# 6_half_bridge.net
KiCad netlist of a schematic drawn in Altium Designer
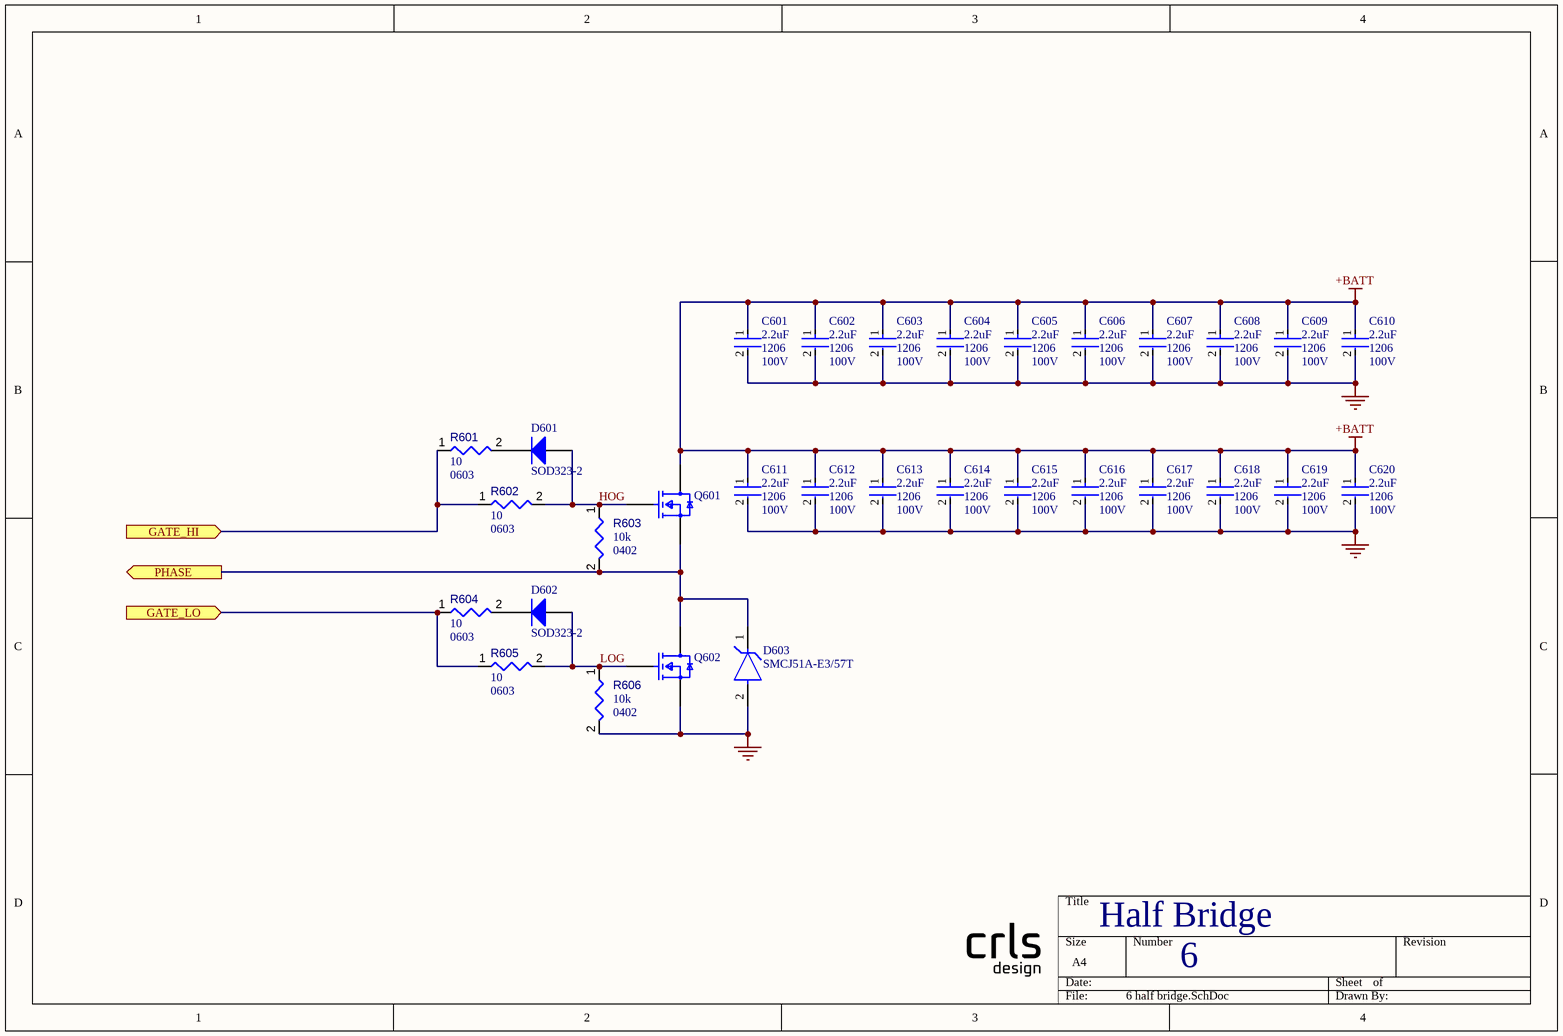
[diagram p0: 6 half bridge.SchDoc]

(export (version "E")
  (design (tool "Eeschema 10.0.6"))
  (components
    (comp (ref "C601")
      (value "CC1206KKX7R0BB225")
      (footprint "FP-CC1206-0_3-1_9-MFG")
      (description "CAP CER 2.2UF 100V X7R 1206")
      (fields
        (field (name "VOLTAGE RATING") "100V")
        (field (name "CASE/PACKAGE") "1206")
        (field (name "CAPACITANCE") "2.2uF")
        (field (name "TOLERANCE") "10%")
      )
      (libsource (lib "Altium Content Vault") (part "b4654b650e69147ec39a6b967a45e02"))
    )
    (comp (ref "C602")
      (value "CC1206KKX7R0BB225")
      (footprint "FP-CC1206-0_3-1_9-MFG")
      (description "CAP CER 2.2UF 100V X7R 1206")
      (fields
        (field (name "VOLTAGE RATING") "100V")
        (field (name "CASE/PACKAGE") "1206")
        (field (name "CAPACITANCE") "2.2uF")
        (field (name "TOLERANCE") "10%")
      )
      (libsource (lib "Altium Content Vault") (part "b4654b650e69147ec39a6b967a45e02"))
    )
    (comp (ref "C603")
      (value "CC1206KKX7R0BB225")
      (footprint "FP-CC1206-0_3-1_9-MFG")
      (description "CAP CER 2.2UF 100V X7R 1206")
      (fields
        (field (name "VOLTAGE RATING") "100V")
        (field (name "CASE/PACKAGE") "1206")
        (field (name "CAPACITANCE") "2.2uF")
        (field (name "TOLERANCE") "10%")
      )
      (libsource (lib "Altium Content Vault") (part "b4654b650e69147ec39a6b967a45e02"))
    )
    (comp (ref "C604")
      (value "CC1206KKX7R0BB225")
      (footprint "FP-CC1206-0_3-1_9-MFG")
      (description "CAP CER 2.2UF 100V X7R 1206")
      (fields
        (field (name "VOLTAGE RATING") "100V")
        (field (name "CASE/PACKAGE") "1206")
        (field (name "CAPACITANCE") "2.2uF")
        (field (name "TOLERANCE") "10%")
      )
      (libsource (lib "Altium Content Vault") (part "b4654b650e69147ec39a6b967a45e02"))
    )
    (comp (ref "C605")
      (value "CC1206KKX7R0BB225")
      (footprint "FP-CC1206-0_3-1_9-MFG")
      (description "CAP CER 2.2UF 100V X7R 1206")
      (fields
        (field (name "VOLTAGE RATING") "100V")
        (field (name "CASE/PACKAGE") "1206")
        (field (name "CAPACITANCE") "2.2uF")
        (field (name "TOLERANCE") "10%")
      )
      (libsource (lib "Altium Content Vault") (part "b4654b650e69147ec39a6b967a45e02"))
    )
    (comp (ref "C606")
      (value "CC1206KKX7R0BB225")
      (footprint "FP-CC1206-0_3-1_9-MFG")
      (description "CAP CER 2.2UF 100V X7R 1206")
      (fields
        (field (name "VOLTAGE RATING") "100V")
        (field (name "CASE/PACKAGE") "1206")
        (field (name "CAPACITANCE") "2.2uF")
        (field (name "TOLERANCE") "10%")
      )
      (libsource (lib "Altium Content Vault") (part "b4654b650e69147ec39a6b967a45e02"))
    )
    (comp (ref "C607")
      (value "CC1206KKX7R0BB225")
      (footprint "FP-CC1206-0_3-1_9-MFG")
      (description "CAP CER 2.2UF 100V X7R 1206")
      (fields
        (field (name "VOLTAGE RATING") "100V")
        (field (name "CASE/PACKAGE") "1206")
        (field (name "CAPACITANCE") "2.2uF")
        (field (name "TOLERANCE") "10%")
      )
      (libsource (lib "Altium Content Vault") (part "b4654b650e69147ec39a6b967a45e02"))
    )
    (comp (ref "C608")
      (value "CC1206KKX7R0BB225")
      (footprint "FP-CC1206-0_3-1_9-MFG")
      (description "CAP CER 2.2UF 100V X7R 1206")
      (fields
        (field (name "VOLTAGE RATING") "100V")
        (field (name "CASE/PACKAGE") "1206")
        (field (name "CAPACITANCE") "2.2uF")
        (field (name "TOLERANCE") "10%")
      )
      (libsource (lib "Altium Content Vault") (part "b4654b650e69147ec39a6b967a45e02"))
    )
    (comp (ref "C609")
      (value "CC1206KKX7R0BB225")
      (footprint "FP-CC1206-0_3-1_9-MFG")
      (description "CAP CER 2.2UF 100V X7R 1206")
      (fields
        (field (name "VOLTAGE RATING") "100V")
        (field (name "CASE/PACKAGE") "1206")
        (field (name "CAPACITANCE") "2.2uF")
        (field (name "TOLERANCE") "10%")
      )
      (libsource (lib "Altium Content Vault") (part "b4654b650e69147ec39a6b967a45e02"))
    )
    (comp (ref "C610")
      (value "CC1206KKX7R0BB225")
      (footprint "FP-CC1206-0_3-1_9-MFG")
      (description "CAP CER 2.2UF 100V X7R 1206")
      (fields
        (field (name "VOLTAGE RATING") "100V")
        (field (name "CASE/PACKAGE") "1206")
        (field (name "CAPACITANCE") "2.2uF")
        (field (name "TOLERANCE") "10%")
      )
      (libsource (lib "Altium Content Vault") (part "b4654b650e69147ec39a6b967a45e02"))
    )
    (comp (ref "C611")
      (value "CC1206KKX7R0BB225")
      (footprint "FP-CC1206-0_3-1_9-MFG")
      (description "CAP CER 2.2UF 100V X7R 1206")
      (fields
        (field (name "VOLTAGE RATING") "100V")
        (field (name "CASE/PACKAGE") "1206")
        (field (name "CAPACITANCE") "2.2uF")
        (field (name "TOLERANCE") "10%")
      )
      (libsource (lib "Altium Content Vault") (part "b4654b650e69147ec39a6b967a45e02"))
    )
    (comp (ref "C612")
      (value "CC1206KKX7R0BB225")
      (footprint "FP-CC1206-0_3-1_9-MFG")
      (description "CAP CER 2.2UF 100V X7R 1206")
      (fields
        (field (name "VOLTAGE RATING") "100V")
        (field (name "CASE/PACKAGE") "1206")
        (field (name "CAPACITANCE") "2.2uF")
        (field (name "TOLERANCE") "10%")
      )
      (libsource (lib "Altium Content Vault") (part "b4654b650e69147ec39a6b967a45e02"))
    )
    (comp (ref "C613")
      (value "CC1206KKX7R0BB225")
      (footprint "FP-CC1206-0_3-1_9-MFG")
      (description "CAP CER 2.2UF 100V X7R 1206")
      (fields
        (field (name "VOLTAGE RATING") "100V")
        (field (name "CASE/PACKAGE") "1206")
        (field (name "CAPACITANCE") "2.2uF")
        (field (name "TOLERANCE") "10%")
      )
      (libsource (lib "Altium Content Vault") (part "b4654b650e69147ec39a6b967a45e02"))
    )
    (comp (ref "C614")
      (value "CC1206KKX7R0BB225")
      (footprint "FP-CC1206-0_3-1_9-MFG")
      (description "CAP CER 2.2UF 100V X7R 1206")
      (fields
        (field (name "VOLTAGE RATING") "100V")
        (field (name "CASE/PACKAGE") "1206")
        (field (name "CAPACITANCE") "2.2uF")
        (field (name "TOLERANCE") "10%")
      )
      (libsource (lib "Altium Content Vault") (part "b4654b650e69147ec39a6b967a45e02"))
    )
    (comp (ref "C615")
      (value "CC1206KKX7R0BB225")
      (footprint "FP-CC1206-0_3-1_9-MFG")
      (description "CAP CER 2.2UF 100V X7R 1206")
      (fields
        (field (name "VOLTAGE RATING") "100V")
        (field (name "CASE/PACKAGE") "1206")
        (field (name "CAPACITANCE") "2.2uF")
        (field (name "TOLERANCE") "10%")
      )
      (libsource (lib "Altium Content Vault") (part "b4654b650e69147ec39a6b967a45e02"))
    )
    (comp (ref "C616")
      (value "CC1206KKX7R0BB225")
      (footprint "FP-CC1206-0_3-1_9-MFG")
      (description "CAP CER 2.2UF 100V X7R 1206")
      (fields
        (field (name "VOLTAGE RATING") "100V")
        (field (name "CASE/PACKAGE") "1206")
        (field (name "CAPACITANCE") "2.2uF")
        (field (name "TOLERANCE") "10%")
      )
      (libsource (lib "Altium Content Vault") (part "b4654b650e69147ec39a6b967a45e02"))
    )
    (comp (ref "C617")
      (value "CC1206KKX7R0BB225")
      (footprint "FP-CC1206-0_3-1_9-MFG")
      (description "CAP CER 2.2UF 100V X7R 1206")
      (fields
        (field (name "VOLTAGE RATING") "100V")
        (field (name "CASE/PACKAGE") "1206")
        (field (name "CAPACITANCE") "2.2uF")
        (field (name "TOLERANCE") "10%")
      )
      (libsource (lib "Altium Content Vault") (part "b4654b650e69147ec39a6b967a45e02"))
    )
    (comp (ref "C618")
      (value "CC1206KKX7R0BB225")
      (footprint "FP-CC1206-0_3-1_9-MFG")
      (description "CAP CER 2.2UF 100V X7R 1206")
      (fields
        (field (name "VOLTAGE RATING") "100V")
        (field (name "CASE/PACKAGE") "1206")
        (field (name "CAPACITANCE") "2.2uF")
        (field (name "TOLERANCE") "10%")
      )
      (libsource (lib "Altium Content Vault") (part "b4654b650e69147ec39a6b967a45e02"))
    )
    (comp (ref "C619")
      (value "CC1206KKX7R0BB225")
      (footprint "FP-CC1206-0_3-1_9-MFG")
      (description "CAP CER 2.2UF 100V X7R 1206")
      (fields
        (field (name "VOLTAGE RATING") "100V")
        (field (name "CASE/PACKAGE") "1206")
        (field (name "CAPACITANCE") "2.2uF")
        (field (name "TOLERANCE") "10%")
      )
      (libsource (lib "Altium Content Vault") (part "b4654b650e69147ec39a6b967a45e02"))
    )
    (comp (ref "C620")
      (value "CC1206KKX7R0BB225")
      (footprint "FP-CC1206-0_3-1_9-MFG")
      (description "CAP CER 2.2UF 100V X7R 1206")
      (fields
        (field (name "VOLTAGE RATING") "100V")
        (field (name "CASE/PACKAGE") "1206")
        (field (name "CAPACITANCE") "2.2uF")
        (field (name "TOLERANCE") "10%")
      )
      (libsource (lib "Altium Content Vault") (part "b4654b650e69147ec39a6b967a45e02"))
    )
    (comp (ref "D601")
      (value "1N4148WS-7-F")
      (footprint "DIOD-SOD323-2-A_V")
      (description "Fast Switching Diode, 75 V, 0.3 A, -65 to 150 degC, 2-Pin SOD323, RoHS, Tape and Reel")
      (fields (field (name "PACKAGEREFERENCE") "SOD323-2"))
      (libsource (lib "Altium Content Vault") (part "D-AK-2"))
    )
    (comp (ref "D602")
      (value "1N4148WS-7-F")
      (footprint "DIOD-SOD323-2-A_V")
      (description "Fast Switching Diode, 75 V, 0.3 A, -65 to 150 degC, 2-Pin SOD323, RoHS, Tape and Reel")
      (fields (field (name "PACKAGEREFERENCE") "SOD323-2"))
      (libsource (lib "Altium Content Vault") (part "D-AK-2"))
    )
    (comp (ref "D603")
      (value "SMCJ51A-E3/57T")
      (footprint "FP-95402-MFG")
      (description "TVS DIODE 51V 82.4V DO214AB")
      (fields
        (field (name "OCTOPART") "https://octopart.com/smcj51a-e3%2F57t-vishay-39559249")
        (field (name "MANUFACTURER") "Vishay")
      )
      (libsource (lib "Altium Content Vault") (part "f813f71cba58e380607f5dd3caf9714"))
    )
    (comp (ref "Q601")
      (value "IAUT300N10S5N015ATMA1")
      (footprint "FP-PG-HSOF-8-MFG")
      (description "100V 300A 1.5MOHM TOLL")
      (fields
        (field (name "MANUFACTURER") "Infineon")
        (field (name "OCTOPART") "https://octopart.com/iaut300n10s5n015atma1-infineon-88797377")
      )
      (libsource (lib "Altium Content Vault") (part "a69337ebdc374053804de1861ec3864"))
    )
    (comp (ref "Q602")
      (value "IAUT300N10S5N015ATMA1")
      (footprint "FP-PG-HSOF-8-MFG")
      (description "100V 300A 1.5MOHM TOLL")
      (fields
        (field (name "MANUFACTURER") "Infineon")
        (field (name "OCTOPART") "https://octopart.com/iaut300n10s5n015atma1-infineon-88797377")
      )
      (libsource (lib "Altium Content Vault") (part "a69337ebdc374053804de1861ec3864"))
    )
    (comp (ref "R601")
      (value "10")
      (footprint "RESC0603(1608)_L")
      (description "Resistor")
      (fields
        (field (name "CASE/PACKAGE") "0603")
        (field (name "TOLERANCE") "1%")
        (field (name "Comment") "Resistors,0603,1%,10")
      )
      (libsource (lib "UBC Uncrewed Aircraft Systems") (part "RES-2"))
    )
    (comp (ref "R602")
      (value "10")
      (footprint "RESC0603(1608)_L")
      (description "Resistor")
      (fields
        (field (name "CASE/PACKAGE") "0603")
        (field (name "TOLERANCE") "1%")
        (field (name "Comment") "Resistors,0603,1%,10")
      )
      (libsource (lib "UBC Uncrewed Aircraft Systems") (part "RES-2"))
    )
    (comp (ref "R603")
      (value "10k")
      (footprint "RESC0402(1005)_L")
      (description "Resistor")
      (fields
        (field (name "CASE/PACKAGE") "0402")
        (field (name "TOLERANCE") "1%")
        (field (name "Comment") "Resistors,0402,1%,10k")
      )
      (libsource (lib "UBC Uncrewed Aircraft Systems") (part "RES-2"))
    )
    (comp (ref "R604")
      (value "10")
      (footprint "RESC0603(1608)_L")
      (description "Resistor")
      (fields
        (field (name "CASE/PACKAGE") "0603")
        (field (name "TOLERANCE") "1%")
        (field (name "Comment") "Resistors,0603,1%,10")
      )
      (libsource (lib "UBC Uncrewed Aircraft Systems") (part "RES-2"))
    )
    (comp (ref "R605")
      (value "10")
      (footprint "RESC0603(1608)_L")
      (description "Resistor")
      (fields
        (field (name "CASE/PACKAGE") "0603")
        (field (name "TOLERANCE") "1%")
        (field (name "Comment") "Resistors,0603,1%,10")
      )
      (libsource (lib "UBC Uncrewed Aircraft Systems") (part "RES-2"))
    )
    (comp (ref "R606")
      (value "10k")
      (footprint "RESC0402(1005)_L")
      (description "Resistor")
      (fields
        (field (name "CASE/PACKAGE") "0402")
        (field (name "TOLERANCE") "1%")
        (field (name "Comment") "Resistors,0402,1%,10k")
      )
      (libsource (lib "UBC Uncrewed Aircraft Systems") (part "RES-2"))
    )
  )
  (nets
    (net (code "1") (name "+BATT") (class "Default")
      (node (ref "C601") (pin "1") (pinfunction "1_1") (pintype "passive"))
      (node (ref "C602") (pin "1") (pinfunction "1_1") (pintype "passive"))
      (node (ref "C603") (pin "1") (pinfunction "1_1") (pintype "passive"))
      (node (ref "C604") (pin "1") (pinfunction "1_1") (pintype "passive"))
      (node (ref "C605") (pin "1") (pinfunction "1_1") (pintype "passive"))
      (node (ref "C606") (pin "1") (pinfunction "1_1") (pintype "passive"))
      (node (ref "C607") (pin "1") (pinfunction "1_1") (pintype "passive"))
      (node (ref "C608") (pin "1") (pinfunction "1_1") (pintype "passive"))
      (node (ref "C609") (pin "1") (pinfunction "1_1") (pintype "passive"))
      (node (ref "C610") (pin "1") (pinfunction "1_1") (pintype "passive"))
      (node (ref "C611") (pin "1") (pinfunction "1_1") (pintype "passive"))
      (node (ref "C612") (pin "1") (pinfunction "1_1") (pintype "passive"))
      (node (ref "C613") (pin "1") (pinfunction "1_1") (pintype "passive"))
      (node (ref "C614") (pin "1") (pinfunction "1_1") (pintype "passive"))
      (node (ref "C615") (pin "1") (pinfunction "1_1") (pintype "passive"))
      (node (ref "C616") (pin "1") (pinfunction "1_1") (pintype "passive"))
      (node (ref "C617") (pin "1") (pinfunction "1_1") (pintype "passive"))
      (node (ref "C618") (pin "1") (pinfunction "1_1") (pintype "passive"))
      (node (ref "C619") (pin "1") (pinfunction "1_1") (pintype "passive"))
      (node (ref "C620") (pin "1") (pinfunction "1_1") (pintype "passive"))
      (node (ref "Q601") (pin "9") (pinfunction "DRAIN_9") (pintype "passive"))
    )
    (net (code "2") (name "/GATE_HI") (class "Default")
      (node (ref "R601") (pin "1") (pinfunction "1_1") (pintype "passive"))
      (node (ref "R602") (pin "1") (pinfunction "1_1") (pintype "passive"))
    )
    (net (code "3") (name "/GATE_LO") (class "Default")
      (node (ref "R604") (pin "1") (pinfunction "1_1") (pintype "passive"))
      (node (ref "R605") (pin "1") (pinfunction "1_1") (pintype "passive"))
    )
    (net (code "4") (name "/HOG") (class "Default")
      (node (ref "D601") (pin "1") (pinfunction "A_1") (pintype "passive"))
      (node (ref "Q601") (pin "1") (pinfunction "GATE_1") (pintype "passive"))
      (node (ref "R602") (pin "2") (pinfunction "2_2") (pintype "passive"))
      (node (ref "R603") (pin "1") (pinfunction "1_1") (pintype "passive"))
    )
    (net (code "5") (name "/LOG") (class "Default")
      (node (ref "D602") (pin "1") (pinfunction "A_1") (pintype "passive"))
      (node (ref "Q602") (pin "1") (pinfunction "GATE_1") (pintype "passive"))
      (node (ref "R605") (pin "2") (pinfunction "2_2") (pintype "passive"))
      (node (ref "R606") (pin "1") (pinfunction "1_1") (pintype "passive"))
    )
    (net (code "6") (name "/PHASE") (class "Default")
      (node (ref "D603") (pin "1") (pinfunction "C_1") (pintype "passive"))
      (node (ref "Q601") (pin "2-3-4-5-6-7-8") (pinfunction "SOURCE_2-3-4-5-6-7-8") (pintype "passive"))
      (node (ref "Q602") (pin "9") (pinfunction "DRAIN_9") (pintype "passive"))
      (node (ref "R603") (pin "2") (pinfunction "2_2") (pintype "passive"))
    )
    (net (code "7") (name "GND") (class "Default")
      (node (ref "C601") (pin "2") (pinfunction "2_2") (pintype "passive"))
      (node (ref "C602") (pin "2") (pinfunction "2_2") (pintype "passive"))
      (node (ref "C603") (pin "2") (pinfunction "2_2") (pintype "passive"))
      (node (ref "C604") (pin "2") (pinfunction "2_2") (pintype "passive"))
      (node (ref "C605") (pin "2") (pinfunction "2_2") (pintype "passive"))
      (node (ref "C606") (pin "2") (pinfunction "2_2") (pintype "passive"))
      (node (ref "C607") (pin "2") (pinfunction "2_2") (pintype "passive"))
      (node (ref "C608") (pin "2") (pinfunction "2_2") (pintype "passive"))
      (node (ref "C609") (pin "2") (pinfunction "2_2") (pintype "passive"))
      (node (ref "C610") (pin "2") (pinfunction "2_2") (pintype "passive"))
      (node (ref "C611") (pin "2") (pinfunction "2_2") (pintype "passive"))
      (node (ref "C612") (pin "2") (pinfunction "2_2") (pintype "passive"))
      (node (ref "C613") (pin "2") (pinfunction "2_2") (pintype "passive"))
      (node (ref "C614") (pin "2") (pinfunction "2_2") (pintype "passive"))
      (node (ref "C615") (pin "2") (pinfunction "2_2") (pintype "passive"))
      (node (ref "C616") (pin "2") (pinfunction "2_2") (pintype "passive"))
      (node (ref "C617") (pin "2") (pinfunction "2_2") (pintype "passive"))
      (node (ref "C618") (pin "2") (pinfunction "2_2") (pintype "passive"))
      (node (ref "C619") (pin "2") (pinfunction "2_2") (pintype "passive"))
      (node (ref "C620") (pin "2") (pinfunction "2_2") (pintype "passive"))
      (node (ref "D603") (pin "2") (pinfunction "A_2") (pintype "passive"))
      (node (ref "Q602") (pin "2-3-4-5-6-7-8") (pinfunction "SOURCE_2-3-4-5-6-7-8") (pintype "passive"))
      (node (ref "R606") (pin "2") (pinfunction "2_2") (pintype "passive"))
    )
    (net (code "8") (name "Net-(D601-K)") (class "Default")
      (node (ref "D601") (pin "2") (pinfunction "K_2") (pintype "passive"))
      (node (ref "R601") (pin "2") (pinfunction "2_2") (pintype "passive"))
    )
    (net (code "9") (name "Net-(D602-K)") (class "Default")
      (node (ref "D602") (pin "2") (pinfunction "K_2") (pintype "passive"))
      (node (ref "R604") (pin "2") (pinfunction "2_2") (pintype "passive"))
    )
  )
)
